# EEG.net
KiCad netlist of a schematic drawn in EAGLE
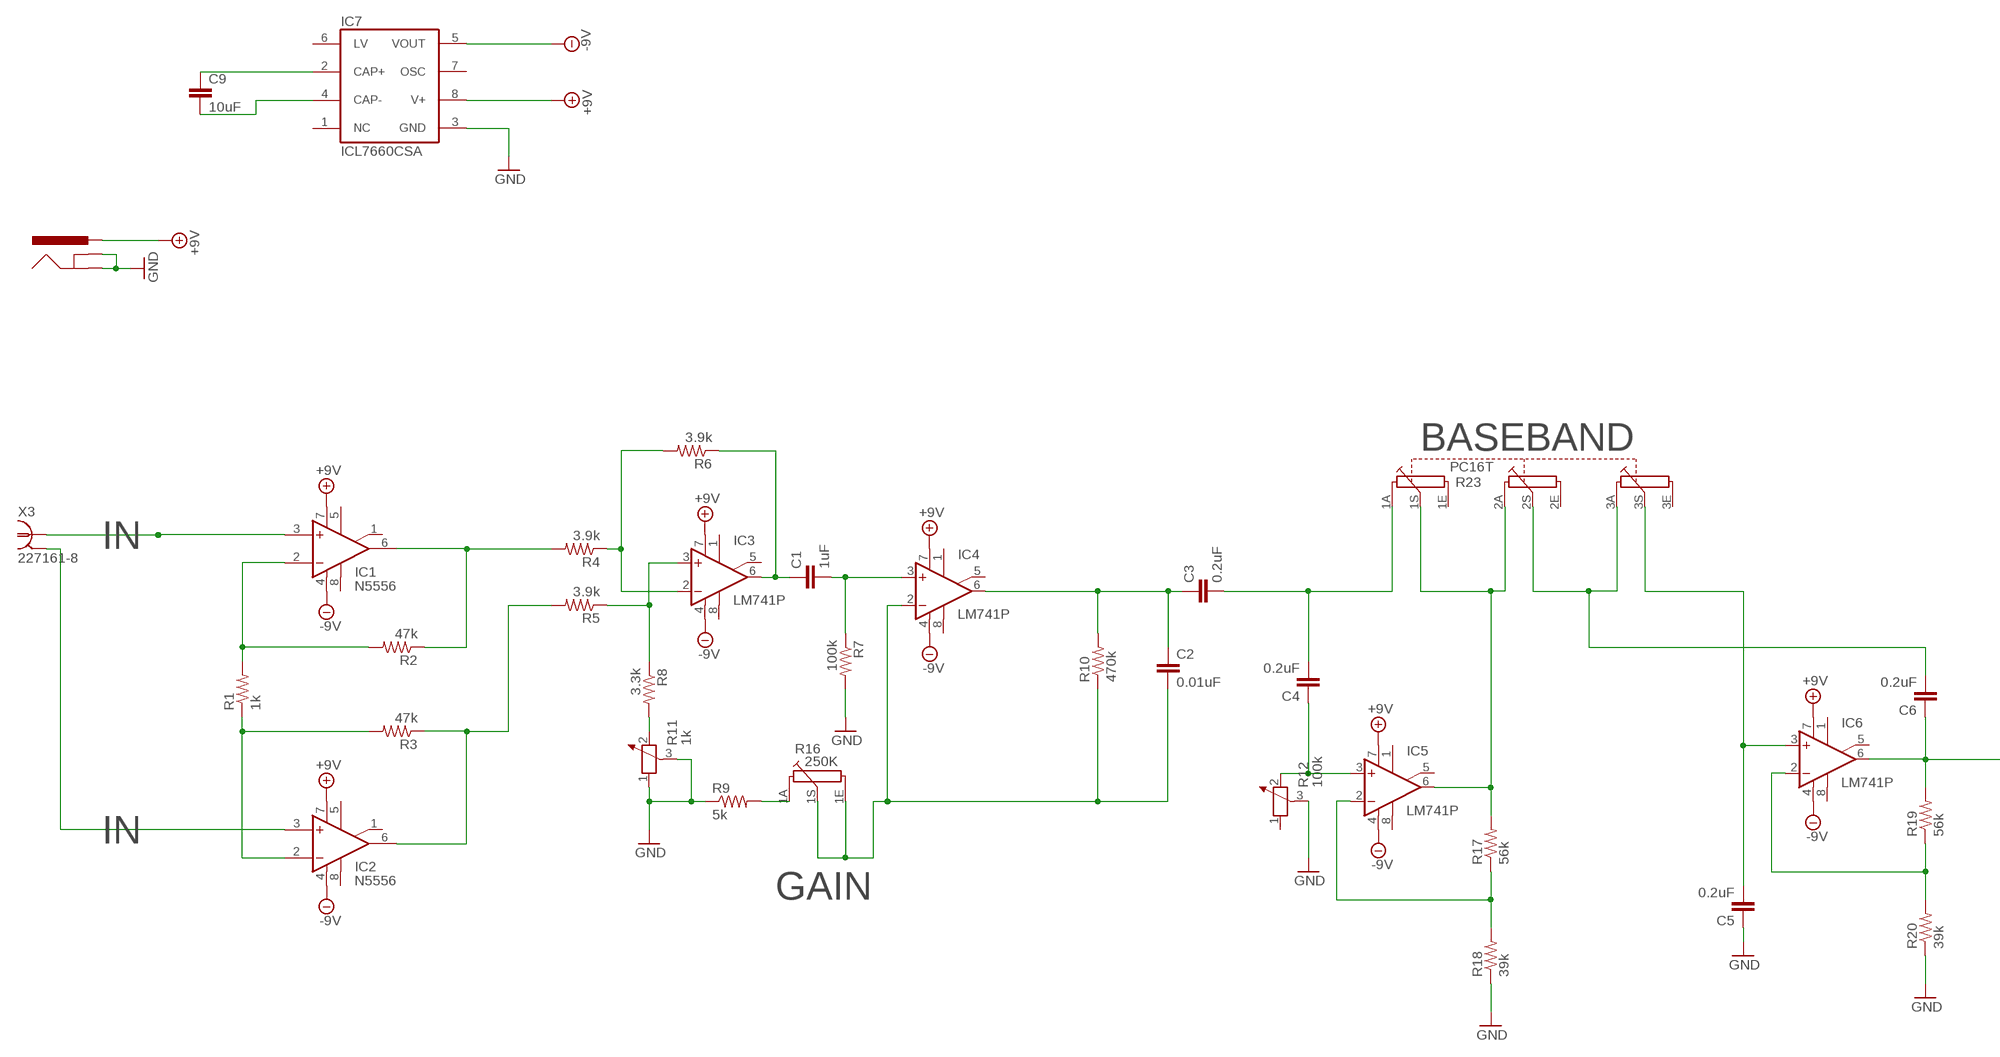
[diagram p0: schematic, sheet 1, part 1 of 2]
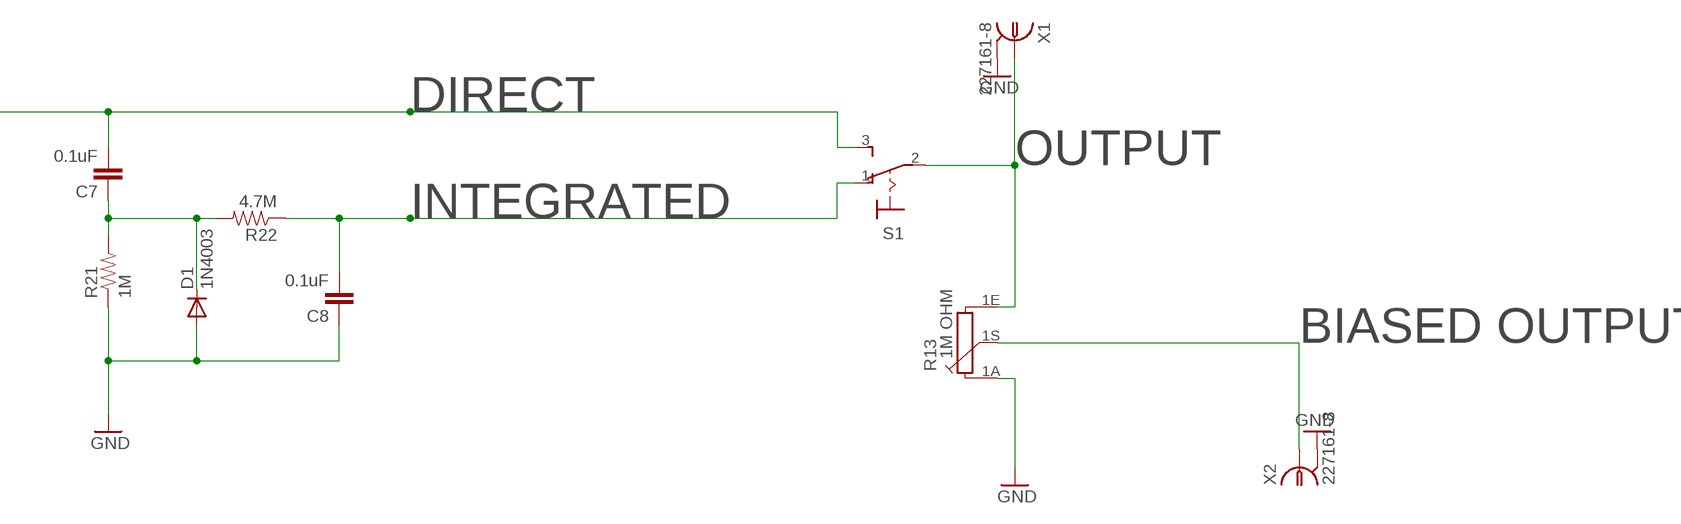
[diagram p1: schematic, sheet 1, part 2 of 2]

(export (version "E")
  (design (tool "Eeschema 10.0.6"))
  (components
    (comp (ref "C1")
      (value "1uF")
      (footprint "eagle-import:C1206")
      (libsource (lib "eagle-import") (part "resistor_C-EUC1206"))
    )
    (comp (ref "C2")
      (value "0.01uF")
      (footprint "eagle-import:C1206")
      (libsource (lib "eagle-import") (part "resistor_C-EUC1206"))
    )
    (comp (ref "C3")
      (value "0.2uF")
      (footprint "eagle-import:C1206")
      (libsource (lib "eagle-import") (part "resistor_C-EUC1206"))
    )
    (comp (ref "C4")
      (value "0.2uF")
      (footprint "eagle-import:C1206")
      (libsource (lib "eagle-import") (part "resistor_C-EUC1206"))
    )
    (comp (ref "C5")
      (value "0.2uF")
      (footprint "eagle-import:C1206")
      (libsource (lib "eagle-import") (part "resistor_C-EUC1206"))
    )
    (comp (ref "C6")
      (value "0.2uF")
      (footprint "eagle-import:C1206")
      (libsource (lib "eagle-import") (part "resistor_C-EUC1206"))
    )
    (comp (ref "C7")
      (value "0.1uF")
      (footprint "eagle-import:C1206")
      (libsource (lib "eagle-import") (part "resistor_C-EUC1206"))
    )
    (comp (ref "C8")
      (value "0.1uF")
      (footprint "eagle-import:C1206")
      (libsource (lib "eagle-import") (part "resistor_C-EUC1206"))
    )
    (comp (ref "C9")
      (value "10uF")
      (footprint "eagle-import:C1206")
      (libsource (lib "eagle-import") (part "C-EUC1206"))
    )
    (comp (ref "D1")
      (value "1N4003")
      (footprint "eagle-import:DO41-10")
      (libsource (lib "eagle-import") (part "1N4004"))
    )
    (comp (ref "IC1")
      (value "N5556")
      (footprint "eagle-import:DIL08")
      (libsource (lib "eagle-import") (part "MAX430CPA"))
    )
    (comp (ref "IC2")
      (value "N5556")
      (footprint "eagle-import:DIL08")
      (fields (field (name "OC_FARNELL") "unknown") (field (name "OC_NEWARK") "unknown"))
      (libsource (lib "eagle-import") (part "MAX430CPA"))
    )
    (comp (ref "IC3")
      (value "LM741P")
      (footprint "eagle-import:DIL08")
      (libsource (lib "eagle-import") (part "741PLM"))
    )
    (comp (ref "IC4")
      (value "LM741P")
      (footprint "eagle-import:DIL08")
      (libsource (lib "eagle-import") (part "741PLM"))
    )
    (comp (ref "IC5")
      (value "LM741P")
      (footprint "eagle-import:DIL08")
      (libsource (lib "eagle-import") (part "741PLM"))
    )
    (comp (ref "IC6")
      (value "LM741P")
      (footprint "eagle-import:DIL08")
      (libsource (lib "eagle-import") (part "741PLM"))
    )
    (comp (ref "IC7")
      (value "ICL7660CSA")
      (footprint "eagle-import:SO08")
      (fields (field (name "MF") "MAXIM"))
      (libsource (lib "eagle-import") (part "ICL7660CSA"))
    )
    (comp (ref "J1")
      (value "SPARKFUN_POWER_JACKPTH")
      (footprint "eagle-import:SPARKFUN_POWER_JACK_PTH")
      (libsource (lib "eagle-import") (part "SPARKFUN_POWER_JACKPTH"))
    )
    (comp (ref "R1")
      (value "1k")
      (footprint "eagle-import:SPARKFUN_1206")
      (libsource (lib "eagle-import") (part "SPARKFUN_RESISTOR1206"))
    )
    (comp (ref "R2")
      (value "47k")
      (footprint "eagle-import:SPARKFUN_1206")
      (libsource (lib "eagle-import") (part "SPARKFUN_RESISTOR1206"))
    )
    (comp (ref "R3")
      (value "47k")
      (footprint "eagle-import:SPARKFUN_1206")
      (libsource (lib "eagle-import") (part "SPARKFUN_RESISTOR1206"))
    )
    (comp (ref "R4")
      (value "3.9k")
      (footprint "eagle-import:SPARKFUN_1206")
      (libsource (lib "eagle-import") (part "SPARKFUN_RESISTOR1206"))
    )
    (comp (ref "R5")
      (value "3.9k")
      (footprint "eagle-import:SPARKFUN_1206")
      (libsource (lib "eagle-import") (part "SPARKFUN_RESISTOR1206"))
    )
    (comp (ref "R6")
      (value "3.9k")
      (footprint "eagle-import:SPARKFUN_1206")
      (libsource (lib "eagle-import") (part "SPARKFUN_RESISTOR1206"))
    )
    (comp (ref "R7")
      (value "100k")
      (footprint "eagle-import:SPARKFUN_1206")
      (libsource (lib "eagle-import") (part "SPARKFUN_RESISTOR1206"))
    )
    (comp (ref "R8")
      (value "3.3k")
      (footprint "eagle-import:SPARKFUN_1206")
      (libsource (lib "eagle-import") (part "SPARKFUN_RESISTOR1206"))
    )
    (comp (ref "R9")
      (value "5k")
      (footprint "eagle-import:SPARKFUN_1206")
      (libsource (lib "eagle-import") (part "SPARKFUN_RESISTOR1206"))
    )
    (comp (ref "R10")
      (value "470k")
      (footprint "eagle-import:SPARKFUN_1206")
      (libsource (lib "eagle-import") (part "SPARKFUN_RESISTOR1206"))
    )
    (comp (ref "R11")
      (value "1k")
      (footprint "eagle-import:PT-10")
      (libsource (lib "eagle-import") (part "POTENTIOMETER_PT-10"))
    )
    (comp (ref "R12")
      (value "100k")
      (footprint "eagle-import:PT-10")
      (libsource (lib "eagle-import") (part "POTENTIOMETER_PT-10"))
    )
    (comp (ref "R13")
      (value "1M OHM")
      (footprint "eagle-import:PC16S")
      (libsource (lib "eagle-import") (part "PC16S"))
    )
    (comp (ref "R16")
      (value "250K")
      (footprint "eagle-import:PC16S")
      (fields (field (name "OC_FARNELL") "4452940") (field (name "OC_NEWARK") "unknown"))
      (libsource (lib "eagle-import") (part "PC16S"))
    )
    (comp (ref "R17")
      (value "56k")
      (footprint "eagle-import:SPARKFUN_1206")
      (libsource (lib "eagle-import") (part "SPARKFUN_RESISTOR1206"))
    )
    (comp (ref "R18")
      (value "39k")
      (footprint "eagle-import:SPARKFUN_1206")
      (libsource (lib "eagle-import") (part "SPARKFUN_RESISTOR1206"))
    )
    (comp (ref "R19")
      (value "56k")
      (footprint "eagle-import:SPARKFUN_1206")
      (libsource (lib "eagle-import") (part "SPARKFUN_RESISTOR1206"))
    )
    (comp (ref "R20")
      (value "39k")
      (footprint "eagle-import:SPARKFUN_1206")
      (libsource (lib "eagle-import") (part "SPARKFUN_RESISTOR1206"))
    )
    (comp (ref "R21")
      (value "1M")
      (footprint "eagle-import:SPARKFUN_1206")
      (libsource (lib "eagle-import") (part "SPARKFUN_RESISTOR1206"))
    )
    (comp (ref "R22")
      (value "4.7M")
      (footprint "eagle-import:SPARKFUN_1206")
      (libsource (lib "eagle-import") (part "SPARKFUN_RESISTOR1206"))
    )
    (comp (ref "R23")
      (value "PC16T")
      (footprint "eagle-import:PC16T")
      (libsource (lib "eagle-import") (part "PC16T"))
    )
    (comp (ref "S1")
      (value "M9040P")
      (footprint "eagle-import:M9040P")
      (libsource (lib "eagle-import") (part "M9040P"))
    )
    (comp (ref "X1")
      (value "227161-8")
      (footprint "eagle-import:AMP_227161")
      (libsource (lib "eagle-import") (part "?227161-8"))
    )
    (comp (ref "X2")
      (value "227161-8")
      (footprint "eagle-import:AMP_227161")
      (libsource (lib "eagle-import") (part "?227161-8"))
    )
    (comp (ref "X3")
      (value "227161-8")
      (footprint "eagle-import:AMP_227161")
      (libsource (lib "eagle-import") (part "?227161-8"))
    )
  )
  (nets
    (net (code "1") (name "+9V") (class "Default")
      (node (ref "IC1") (pin "7") (pinfunction "V+_7") (pintype "power_in"))
      (node (ref "IC2") (pin "7") (pinfunction "V+_7") (pintype "power_in"))
      (node (ref "IC3") (pin "7") (pinfunction "V+_7") (pintype "power_in"))
      (node (ref "IC4") (pin "7") (pinfunction "V+_7") (pintype "power_in"))
      (node (ref "IC5") (pin "7") (pinfunction "V+_7") (pintype "power_in"))
      (node (ref "IC6") (pin "7") (pinfunction "V+_7") (pintype "power_in"))
      (node (ref "IC7") (pin "8") (pinfunction "V+_8") (pintype "power_in"))
      (node (ref "J1") (pin "PWR") (pinfunction "PWR_PWR") (pintype "bidirectional"))
    )
    (net (code "2") (name "-9V") (class "Default")
      (node (ref "IC1") (pin "4") (pinfunction "V-_4") (pintype "power_in"))
      (node (ref "IC2") (pin "4") (pinfunction "V-_4") (pintype "power_in"))
      (node (ref "IC3") (pin "4") (pinfunction "V-_4") (pintype "power_in"))
      (node (ref "IC4") (pin "4") (pinfunction "V-_4") (pintype "power_in"))
      (node (ref "IC5") (pin "4") (pinfunction "V-_4") (pintype "power_in"))
      (node (ref "IC6") (pin "4") (pinfunction "V-_4") (pintype "power_in"))
      (node (ref "IC7") (pin "5") (pinfunction "VOUT_5") (pintype "output"))
    )
    (net (code "3") (name "GND") (class "Default")
      (node (ref "C5") (pin "1") (pinfunction "1_1") (pintype "passive"))
      (node (ref "C8") (pin "1") (pinfunction "1_1") (pintype "passive"))
      (node (ref "D1") (pin "A") (pinfunction "A_A") (pintype "passive"))
      (node (ref "IC7") (pin "3") (pinfunction "GND_3") (pintype "power_in"))
      (node (ref "J1") (pin "GND") (pinfunction "GND_GND") (pintype "bidirectional"))
      (node (ref "J1") (pin "GNDBREAK") (pinfunction "GNDBREAK_GNDBREAK") (pintype "bidirectional"))
      (node (ref "R11") (pin "1") (pinfunction "1_1") (pintype "passive"))
      (node (ref "R11") (pin "3") (pinfunction "3_3") (pintype "passive"))
      (node (ref "R12") (pin "3") (pinfunction "3_3") (pintype "passive"))
      (node (ref "R13") (pin "1A") (pinfunction "1A_1A") (pintype "passive"))
      (node (ref "R18") (pin "1") (pinfunction "1_1") (pintype "passive"))
      (node (ref "R20") (pin "1") (pinfunction "1_1") (pintype "passive"))
      (node (ref "R21") (pin "1") (pinfunction "1_1") (pintype "passive"))
      (node (ref "R7") (pin "2") (pinfunction "2_2") (pintype "passive"))
      (node (ref "R9") (pin "1") (pinfunction "1_1") (pintype "passive"))
      (node (ref "X1") (pin "2") (pinfunction "GND_2") (pintype "power_in"))
      (node (ref "X2") (pin "2") (pinfunction "GND_2") (pintype "power_in"))
    )
    (net (code "4") (name "Net-(C3-Pad2)") (class "Default")
      (node (ref "C3") (pin "2") (pinfunction "2_2") (pintype "passive"))
      (node (ref "C4") (pin "2") (pinfunction "2_2") (pintype "passive"))
      (node (ref "R23") (pin "1A") (pinfunction "1A_1A") (pintype "passive"))
    )
    (net (code "5") (name "Net-(C6-Pad2)") (class "Default")
      (node (ref "C6") (pin "2") (pinfunction "2_2") (pintype "passive"))
      (node (ref "R23") (pin "2S") (pinfunction "2S_2S") (pintype "passive"))
      (node (ref "R23") (pin "3A") (pinfunction "3A_3A") (pintype "passive"))
    )
    (net (code "6") (name "Net-(C7-Pad1)") (class "Default")
      (node (ref "C7") (pin "1") (pinfunction "1_1") (pintype "passive"))
      (node (ref "D1") (pin "C") (pinfunction "C_C") (pintype "passive"))
      (node (ref "R21") (pin "2") (pinfunction "2_2") (pintype "passive"))
      (node (ref "R22") (pin "2") (pinfunction "2_2") (pintype "passive"))
    )
    (net (code "7") (name "Net-(IC1-+IN)") (class "Default")
      (node (ref "IC1") (pin "3") (pinfunction "+IN_3") (pintype "input"))
      (node (ref "X3") (pin "1") (pinfunction "1_1") (pintype "passive"))
    )
    (net (code "8") (name "Net-(IC1--IN)") (class "Default")
      (node (ref "IC1") (pin "2") (pinfunction "-IN_2") (pintype "input"))
      (node (ref "R1") (pin "2") (pinfunction "2_2") (pintype "passive"))
      (node (ref "R2") (pin "2") (pinfunction "2_2") (pintype "passive"))
    )
    (net (code "9") (name "Net-(IC1-OUT)") (class "Default")
      (node (ref "IC1") (pin "6") (pinfunction "OUT_6") (pintype "output"))
      (node (ref "R2") (pin "1") (pinfunction "1_1") (pintype "passive"))
      (node (ref "R4") (pin "2") (pinfunction "2_2") (pintype "passive"))
    )
    (net (code "10") (name "Net-(IC2-+IN)") (class "Default")
      (node (ref "IC2") (pin "3") (pinfunction "+IN_3") (pintype "input"))
      (node (ref "X3") (pin "2") (pinfunction "GND_2") (pintype "power_in"))
    )
    (net (code "11") (name "Net-(IC2--IN)") (class "Default")
      (node (ref "IC2") (pin "2") (pinfunction "-IN_2") (pintype "input"))
      (node (ref "R1") (pin "1") (pinfunction "1_1") (pintype "passive"))
      (node (ref "R3") (pin "2") (pinfunction "2_2") (pintype "passive"))
    )
    (net (code "12") (name "Net-(IC2-OUT)") (class "Default")
      (node (ref "IC2") (pin "6") (pinfunction "OUT_6") (pintype "output"))
      (node (ref "R3") (pin "1") (pinfunction "1_1") (pintype "passive"))
      (node (ref "R5") (pin "2") (pinfunction "2_2") (pintype "passive"))
    )
    (net (code "13") (name "Net-(IC3-+IN)") (class "Default")
      (node (ref "IC3") (pin "3") (pinfunction "+IN_3") (pintype "input"))
      (node (ref "R5") (pin "1") (pinfunction "1_1") (pintype "passive"))
      (node (ref "R8") (pin "1") (pinfunction "1_1") (pintype "passive"))
    )
    (net (code "14") (name "Net-(IC3--IN)") (class "Default")
      (node (ref "IC3") (pin "2") (pinfunction "-IN_2") (pintype "input"))
      (node (ref "R4") (pin "1") (pinfunction "1_1") (pintype "passive"))
      (node (ref "R6") (pin "2") (pinfunction "2_2") (pintype "passive"))
    )
    (net (code "15") (name "Net-(IC3-OUT)") (class "Default")
      (node (ref "C1") (pin "1") (pinfunction "1_1") (pintype "passive"))
      (node (ref "IC3") (pin "6") (pinfunction "OUT_6") (pintype "output"))
      (node (ref "R6") (pin "1") (pinfunction "1_1") (pintype "passive"))
    )
    (net (code "16") (name "Net-(IC4-+IN)") (class "Default")
      (node (ref "C1") (pin "2") (pinfunction "2_2") (pintype "passive"))
      (node (ref "IC4") (pin "3") (pinfunction "+IN_3") (pintype "input"))
      (node (ref "R7") (pin "1") (pinfunction "1_1") (pintype "passive"))
    )
    (net (code "17") (name "Net-(IC4--IN)") (class "Default")
      (node (ref "C2") (pin "2") (pinfunction "2_2") (pintype "passive"))
      (node (ref "IC4") (pin "2") (pinfunction "-IN_2") (pintype "input"))
      (node (ref "R10") (pin "1") (pinfunction "1_1") (pintype "passive"))
      (node (ref "R16") (pin "1E") (pinfunction "1E_1E") (pintype "passive"))
      (node (ref "R16") (pin "1S") (pinfunction "1S_1S") (pintype "passive"))
    )
    (net (code "18") (name "Net-(IC4-OUT)") (class "Default")
      (node (ref "C2") (pin "1") (pinfunction "1_1") (pintype "passive"))
      (node (ref "C3") (pin "1") (pinfunction "1_1") (pintype "passive"))
      (node (ref "IC4") (pin "6") (pinfunction "OUT_6") (pintype "output"))
      (node (ref "R10") (pin "2") (pinfunction "2_2") (pintype "passive"))
    )
    (net (code "19") (name "Net-(IC5-+IN)") (class "Default")
      (node (ref "C4") (pin "1") (pinfunction "1_1") (pintype "passive"))
      (node (ref "IC5") (pin "3") (pinfunction "+IN_3") (pintype "input"))
      (node (ref "R12") (pin "2") (pinfunction "2_2") (pintype "passive"))
    )
    (net (code "20") (name "Net-(IC5--IN)") (class "Default")
      (node (ref "IC5") (pin "2") (pinfunction "-IN_2") (pintype "input"))
      (node (ref "R17") (pin "1") (pinfunction "1_1") (pintype "passive"))
      (node (ref "R18") (pin "2") (pinfunction "2_2") (pintype "passive"))
    )
    (net (code "21") (name "Net-(IC5-OUT)") (class "Default")
      (node (ref "IC5") (pin "6") (pinfunction "OUT_6") (pintype "output"))
      (node (ref "R17") (pin "2") (pinfunction "2_2") (pintype "passive"))
      (node (ref "R23") (pin "1S") (pinfunction "1S_1S") (pintype "passive"))
      (node (ref "R23") (pin "2A") (pinfunction "2A_2A") (pintype "passive"))
    )
    (net (code "22") (name "Net-(IC6-+IN)") (class "Default")
      (node (ref "C5") (pin "2") (pinfunction "2_2") (pintype "passive"))
      (node (ref "IC6") (pin "3") (pinfunction "+IN_3") (pintype "input"))
      (node (ref "R23") (pin "3S") (pinfunction "3S_3S") (pintype "passive"))
    )
    (net (code "23") (name "Net-(IC6--IN)") (class "Default")
      (node (ref "IC6") (pin "2") (pinfunction "-IN_2") (pintype "input"))
      (node (ref "R19") (pin "1") (pinfunction "1_1") (pintype "passive"))
      (node (ref "R20") (pin "2") (pinfunction "2_2") (pintype "passive"))
    )
    (net (code "24") (name "Net-(IC6-OUT)") (class "Default")
      (node (ref "C6") (pin "1") (pinfunction "1_1") (pintype "passive"))
      (node (ref "C7") (pin "2") (pinfunction "2_2") (pintype "passive"))
      (node (ref "IC6") (pin "6") (pinfunction "OUT_6") (pintype "output"))
      (node (ref "R19") (pin "2") (pinfunction "2_2") (pintype "passive"))
      (node (ref "S1") (pin "3") (pinfunction "S_3") (pintype "passive"))
    )
    (net (code "25") (name "Net-(IC7-CAP+)") (class "Default")
      (node (ref "C9") (pin "1") (pinfunction "1_1") (pintype "passive"))
      (node (ref "IC7") (pin "2") (pinfunction "CAP+_2") (pintype "passive"))
    )
    (net (code "26") (name "Net-(IC7-CAP-)") (class "Default")
      (node (ref "C9") (pin "2") (pinfunction "2_2") (pintype "passive"))
      (node (ref "IC7") (pin "4") (pinfunction "CAP-_4") (pintype "passive"))
    )
    (net (code "27") (name "Net-(R11-Pad2)") (class "Default")
      (node (ref "R11") (pin "2") (pinfunction "2_2") (pintype "passive"))
      (node (ref "R8") (pin "2") (pinfunction "2_2") (pintype "passive"))
    )
    (net (code "28") (name "Net-(R13-Pad1S)") (class "Default")
      (node (ref "R13") (pin "1S") (pinfunction "1S_1S") (pintype "passive"))
      (node (ref "X2") (pin "1") (pinfunction "1_1") (pintype "passive"))
    )
    (net (code "29") (name "Net-(R16-Pad1A)") (class "Default")
      (node (ref "R16") (pin "1A") (pinfunction "1A_1A") (pintype "passive"))
      (node (ref "R9") (pin "2") (pinfunction "2_2") (pintype "passive"))
    )
    (net (code "30") (name "Net-(S1-O)") (class "Default")
      (node (ref "C8") (pin "2") (pinfunction "2_2") (pintype "passive"))
      (node (ref "R22") (pin "1") (pinfunction "1_1") (pintype "passive"))
      (node (ref "S1") (pin "1") (pinfunction "O_1") (pintype "passive"))
    )
    (net (code "31") (name "Net-(S1-P)") (class "Default")
      (node (ref "R13") (pin "1E") (pinfunction "1E_1E") (pintype "passive"))
      (node (ref "S1") (pin "2") (pinfunction "P_2") (pintype "passive"))
      (node (ref "X1") (pin "1") (pinfunction "1_1") (pintype "passive"))
    )
    (net (code "32") (name "unconnected-(IC1-NC-Pad1)") (class "Default")
      (node (ref "IC1") (pin "1") (pinfunction "NC_1") (pintype "no_connect"))
    )
    (net (code "33") (name "unconnected-(IC1-NC-Pad5)") (class "Default")
      (node (ref "IC1") (pin "5") (pinfunction "NC_5") (pintype "no_connect"))
    )
    (net (code "34") (name "unconnected-(IC1-NC-Pad8)") (class "Default")
      (node (ref "IC1") (pin "8") (pinfunction "NC_8") (pintype "no_connect"))
    )
    (net (code "35") (name "unconnected-(IC2-NC-Pad1)") (class "Default")
      (node (ref "IC2") (pin "1") (pinfunction "NC_1") (pintype "no_connect"))
    )
    (net (code "36") (name "unconnected-(IC2-NC-Pad5)") (class "Default")
      (node (ref "IC2") (pin "5") (pinfunction "NC_5") (pintype "no_connect"))
    )
    (net (code "37") (name "unconnected-(IC2-NC-Pad8)") (class "Default")
      (node (ref "IC2") (pin "8") (pinfunction "NC_8") (pintype "no_connect"))
    )
    (net (code "38") (name "unconnected-(IC3-ON1-Pad1)") (class "Default")
      (node (ref "IC3") (pin "1") (pinfunction "ON1_1") (pintype "passive"))
    )
    (net (code "39") (name "unconnected-(IC3-ON2-Pad5)") (class "Default")
      (node (ref "IC3") (pin "5") (pinfunction "ON2_5") (pintype "passive"))
    )
    (net (code "40") (name "unconnected-(IC3-OPT-Pad8)") (class "Default")
      (node (ref "IC3") (pin "8") (pinfunction "OPT_8") (pintype "passive"))
    )
    (net (code "41") (name "unconnected-(IC4-ON1-Pad1)") (class "Default")
      (node (ref "IC4") (pin "1") (pinfunction "ON1_1") (pintype "passive"))
    )
    (net (code "42") (name "unconnected-(IC4-ON2-Pad5)") (class "Default")
      (node (ref "IC4") (pin "5") (pinfunction "ON2_5") (pintype "passive"))
    )
    (net (code "43") (name "unconnected-(IC4-OPT-Pad8)") (class "Default")
      (node (ref "IC4") (pin "8") (pinfunction "OPT_8") (pintype "passive"))
    )
    (net (code "44") (name "unconnected-(IC5-ON1-Pad1)") (class "Default")
      (node (ref "IC5") (pin "1") (pinfunction "ON1_1") (pintype "passive"))
    )
    (net (code "45") (name "unconnected-(IC5-ON2-Pad5)") (class "Default")
      (node (ref "IC5") (pin "5") (pinfunction "ON2_5") (pintype "passive"))
    )
    (net (code "46") (name "unconnected-(IC5-OPT-Pad8)") (class "Default")
      (node (ref "IC5") (pin "8") (pinfunction "OPT_8") (pintype "passive"))
    )
    (net (code "47") (name "unconnected-(IC6-ON1-Pad1)") (class "Default")
      (node (ref "IC6") (pin "1") (pinfunction "ON1_1") (pintype "passive"))
    )
    (net (code "48") (name "unconnected-(IC6-ON2-Pad5)") (class "Default")
      (node (ref "IC6") (pin "5") (pinfunction "ON2_5") (pintype "passive"))
    )
    (net (code "49") (name "unconnected-(IC6-OPT-Pad8)") (class "Default")
      (node (ref "IC6") (pin "8") (pinfunction "OPT_8") (pintype "passive"))
    )
    (net (code "50") (name "unconnected-(IC7-LV-Pad6)") (class "Default")
      (node (ref "IC7") (pin "6") (pinfunction "LV_6") (pintype "passive"))
    )
    (net (code "51") (name "unconnected-(IC7-NC-Pad1)") (class "Default")
      (node (ref "IC7") (pin "1") (pinfunction "NC_1") (pintype "no_connect"))
    )
    (net (code "52") (name "unconnected-(IC7-OSC-Pad7)") (class "Default")
      (node (ref "IC7") (pin "7") (pinfunction "OSC_7") (pintype "output"))
    )
    (net (code "53") (name "unconnected-(R12-Pad1)") (class "Default")
      (node (ref "R12") (pin "1") (pinfunction "1_1") (pintype "passive"))
    )
    (net (code "54") (name "unconnected-(R23-Pad1E)") (class "Default")
      (node (ref "R23") (pin "1E") (pinfunction "1E_1E") (pintype "passive"))
    )
    (net (code "55") (name "unconnected-(R23-Pad2E)") (class "Default")
      (node (ref "R23") (pin "2E") (pinfunction "2E_2E") (pintype "passive"))
    )
    (net (code "56") (name "unconnected-(R23-Pad3E)") (class "Default")
      (node (ref "R23") (pin "3E") (pinfunction "3E_3E") (pintype "passive"))
    )
  )
)
